# MUDE_-_Rev_A.net
KiCad netlist of a schematic drawn in EAGLE
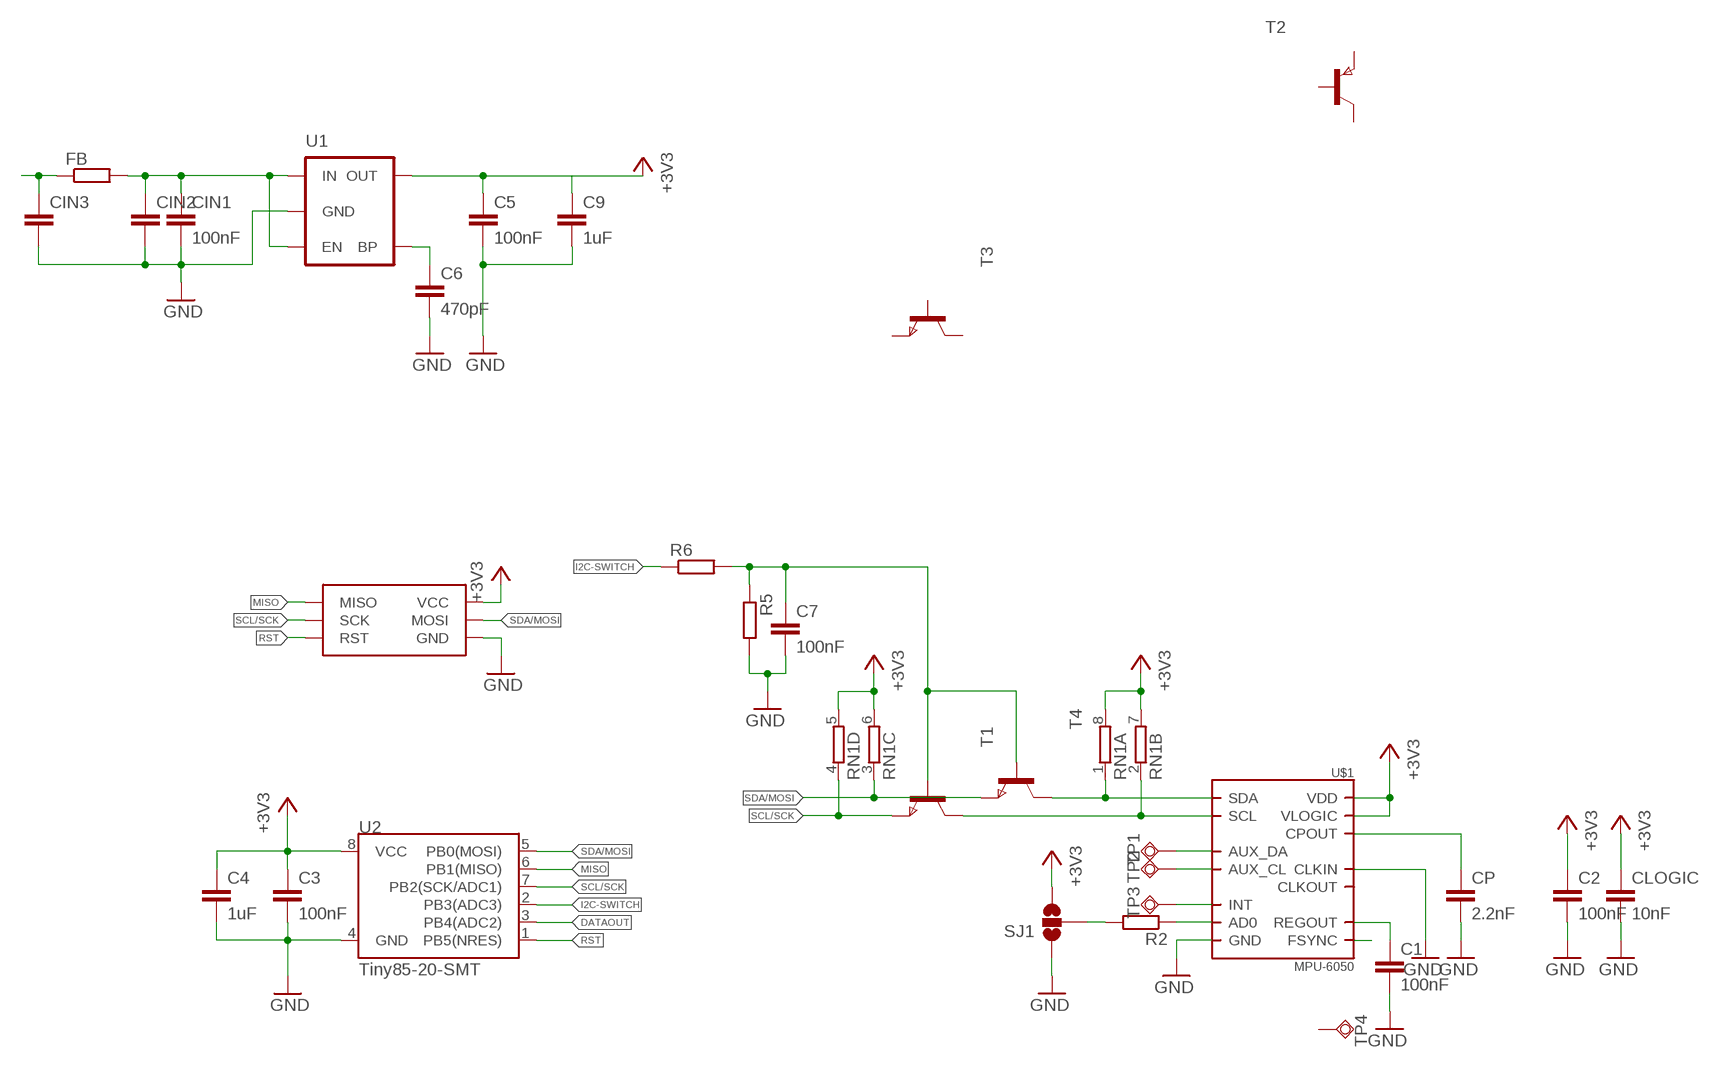
[diagram p0: schematic, sheet 1]

(export (version "E")
  (design (tool "Eeschema 10.0.6"))
  (components
    (comp (ref "C1")
      (value "100nF")
      (footprint "eagle-import:C0603")
      (libsource (lib "eagle-import") (part "C-EUC0603"))
    )
    (comp (ref "C2")
      (value "100nF")
      (footprint "eagle-import:C0603")
      (libsource (lib "eagle-import") (part "C-EUC0603"))
    )
    (comp (ref "C3")
      (value "100nF")
      (footprint "eagle-import:C0603")
      (libsource (lib "eagle-import") (part "C-EUC0603"))
    )
    (comp (ref "C4")
      (value "1uF")
      (footprint "eagle-import:C0603")
      (libsource (lib "eagle-import") (part "C-EUC0603"))
    )
    (comp (ref "C5")
      (value "100nF")
      (footprint "eagle-import:C0603")
      (libsource (lib "eagle-import") (part "C-EUC0603"))
    )
    (comp (ref "C6")
      (value "470pF")
      (footprint "eagle-import:C0603")
      (libsource (lib "eagle-import") (part "C-EUC0603"))
    )
    (comp (ref "C7")
      (value "100nF")
      (footprint "eagle-import:C0603")
      (libsource (lib "eagle-import") (part "C-EUC0603"))
    )
    (comp (ref "C9")
      (value "1uF")
      (footprint "eagle-import:C0603")
      (libsource (lib "eagle-import") (part "C-EUC0603"))
    )
    (comp (ref "CIN1")
      (value "100nF")
      (footprint "eagle-import:C0603")
      (libsource (lib "eagle-import") (part "C-EUC0603"))
    )
    (comp (ref "CIN2")
      (value "C-EUC0805")
      (footprint "eagle-import:C0805")
      (libsource (lib "eagle-import") (part "C-EUC0805"))
    )
    (comp (ref "CIN3")
      (value "C-EUC0805")
      (footprint "eagle-import:C0805")
      (libsource (lib "eagle-import") (part "C-EUC0805"))
    )
    (comp (ref "CLOGIC")
      (value "10nF")
      (footprint "eagle-import:C0603")
      (libsource (lib "eagle-import") (part "C-EUC0603"))
    )
    (comp (ref "CP")
      (value "2.2nF")
      (footprint "eagle-import:C0603")
      (libsource (lib "eagle-import") (part "C-EUC0603"))
    )
    (comp (ref "FB")
      (value "R-EU_R0603")
      (footprint "eagle-import:R0603")
      (libsource (lib "eagle-import") (part "R-EU_R0603"))
    )
    (comp (ref "R2")
      (value "R-EU_R0603")
      (footprint "eagle-import:R0603")
      (libsource (lib "eagle-import") (part "R-EU_R0603"))
    )
    (comp (ref "R5")
      (value "R-EU_R0603")
      (footprint "eagle-import:R0603")
      (libsource (lib "eagle-import") (part "R-EU_R0603"))
    )
    (comp (ref "R6")
      (value "R-EU_R0603")
      (footprint "eagle-import:R0603")
      (libsource (lib "eagle-import") (part "R-EU_R0603"))
    )
    (comp (ref "RN1")
      (value "4R-N0603-ARV")
      (footprint "eagle-import:0603-ARV")
      (libsource (lib "eagle-import") (part "4R-N0603-ARV"))
    )
    (comp (ref "SJ1")
      (value "SOLDERJUMPER_2WAYS")
      (footprint "eagle-import:SJ_3")
      (libsource (lib "eagle-import") (part "SOLDERJUMPER_2WAYS"))
    )
    (comp (ref "T1")
      (value "NPNSOT323")
      (footprint "eagle-import:SOT323")
      (fields (field (name "MPN") "DSS4160U-7"))
      (libsource (lib "eagle-import") (part "NPNSOT323"))
    )
    (comp (ref "T2")
      (value "PNPSOT323")
      (footprint "eagle-import:SOT323")
      (fields (field (name "MPN") "2DB1689-7"))
      (libsource (lib "eagle-import") (part "PNPSOT323"))
    )
    (comp (ref "T3")
      (value "NPNSOT323")
      (footprint "eagle-import:SOT323")
      (fields (field (name "MPN") "DSS4160U-7"))
      (libsource (lib "eagle-import") (part "NPNSOT323"))
    )
    (comp (ref "T4")
      (value "NPNSOT323")
      (footprint "eagle-import:SOT323")
      (fields (field (name "MPN") "DSS4160U-7"))
      (libsource (lib "eagle-import") (part "NPNSOT323"))
    )
    (comp (ref "TP1")
      (value "TPSQTP10R")
      (footprint "eagle-import:TP10R")
      (libsource (lib "eagle-import") (part "TPSQTP10R"))
    )
    (comp (ref "TP2")
      (value "TPSQTP10R")
      (footprint "eagle-import:TP10R")
      (libsource (lib "eagle-import") (part "TPSQTP10R"))
    )
    (comp (ref "TP3")
      (value "TPSQTP10R")
      (footprint "eagle-import:TP10R")
      (libsource (lib "eagle-import") (part "TPSQTP10R"))
    )
    (comp (ref "TP4")
      (value "TPSQTP14R")
      (footprint "eagle-import:TP14R")
      (libsource (lib "eagle-import") (part "TPSQTP14R"))
    )
    (comp (ref "U$1")
      (value "MPU-6050")
      (footprint "eagle-import:QFN.24.4X4")
      (libsource (lib "eagle-import") (part "MPU-6050"))
    )
    (comp (ref "U$3")
      (value "ISP_POGOISP_POGO")
      (footprint "eagle-import:ISP_POGO")
      (libsource (lib "eagle-import") (part "ISP_POGOISP_POGO"))
    )
    (comp (ref "U1")
      (value "MIC52053.3V")
      (footprint "eagle-import:SOT23-5")
      (libsource (lib "eagle-import") (part "MIC52053.3V"))
    )
    (comp (ref "U2")
      (value "Tiny85-20-SMT")
      (footprint "eagle-import:SO08-EIAJ")
      (libsource (lib "eagle-import") (part "ATTINY45TINY85-20-SMT"))
    )
  )
  (nets
    (net (code "1") (name "+3V3") (class "Default")
      (node (ref "C2") (pin "1") (pinfunction "1_1") (pintype "passive"))
      (node (ref "C3") (pin "1") (pinfunction "1_1") (pintype "passive"))
      (node (ref "C4") (pin "1") (pinfunction "1_1") (pintype "passive"))
      (node (ref "C5") (pin "1") (pinfunction "1_1") (pintype "passive"))
      (node (ref "C9") (pin "1") (pinfunction "1_1") (pintype "passive"))
      (node (ref "CLOGIC") (pin "1") (pinfunction "1_1") (pintype "passive"))
      (node (ref "RN1") (pin "5") (pinfunction "2_5") (pintype "passive"))
      (node (ref "RN1") (pin "6") (pinfunction "2_6") (pintype "passive"))
      (node (ref "RN1") (pin "7") (pinfunction "2_7") (pintype "passive"))
      (node (ref "RN1") (pin "8") (pinfunction "2_8") (pintype "passive"))
      (node (ref "SJ1") (pin "3") (pinfunction "3_3") (pintype "passive"))
      (node (ref "U$1") (pin "13") (pinfunction "VDD_13") (pintype "bidirectional"))
      (node (ref "U$1") (pin "8") (pinfunction "VLOGIC_8") (pintype "bidirectional"))
      (node (ref "U$3") (pin "VCC") (pinfunction "VCC_VCC") (pintype "bidirectional"))
      (node (ref "U1") (pin "5") (pinfunction "OUT_5") (pintype "passive"))
      (node (ref "U2") (pin "8") (pinfunction "VCC_8") (pintype "bidirectional"))
    )
    (net (code "2") (name "DATAOUT") (class "Default")
      (node (ref "U2") (pin "3") (pinfunction "PB4(ADC2)_3") (pintype "bidirectional"))
    )
    (net (code "3") (name "GND") (class "Default")
      (node (ref "C1") (pin "2") (pinfunction "2_2") (pintype "passive"))
      (node (ref "C2") (pin "2") (pinfunction "2_2") (pintype "passive"))
      (node (ref "C3") (pin "2") (pinfunction "2_2") (pintype "passive"))
      (node (ref "C4") (pin "2") (pinfunction "2_2") (pintype "passive"))
      (node (ref "C5") (pin "2") (pinfunction "2_2") (pintype "passive"))
      (node (ref "C6") (pin "2") (pinfunction "2_2") (pintype "passive"))
      (node (ref "C7") (pin "2") (pinfunction "2_2") (pintype "passive"))
      (node (ref "C9") (pin "2") (pinfunction "2_2") (pintype "passive"))
      (node (ref "CIN1") (pin "2") (pinfunction "2_2") (pintype "passive"))
      (node (ref "CIN2") (pin "2") (pinfunction "2_2") (pintype "passive"))
      (node (ref "CIN3") (pin "2") (pinfunction "2_2") (pintype "passive"))
      (node (ref "CLOGIC") (pin "2") (pinfunction "2_2") (pintype "passive"))
      (node (ref "CP") (pin "2") (pinfunction "2_2") (pintype "passive"))
      (node (ref "R5") (pin "2") (pinfunction "2_2") (pintype "passive"))
      (node (ref "SJ1") (pin "1") (pinfunction "1_1") (pintype "passive"))
      (node (ref "U$1") (pin "1") (pinfunction "CLKIN_1") (pintype "bidirectional"))
      (node (ref "U$1") (pin "18") (pinfunction "GND_18") (pintype "bidirectional"))
      (node (ref "U$3") (pin "GND") (pinfunction "GND_GND") (pintype "bidirectional"))
      (node (ref "U1") (pin "2") (pinfunction "GND_2") (pintype "input"))
      (node (ref "U2") (pin "4") (pinfunction "GND_4") (pintype "bidirectional"))
    )
    (net (code "4") (name "I2C-SWITCH") (class "Default")
      (node (ref "R6") (pin "1") (pinfunction "1_1") (pintype "passive"))
      (node (ref "U2") (pin "2") (pinfunction "PB3(ADC3)_2") (pintype "bidirectional"))
    )
    (net (code "5") (name "MISO") (class "Default")
      (node (ref "U$3") (pin "MISO") (pinfunction "MISO_MISO") (pintype "bidirectional"))
      (node (ref "U2") (pin "6") (pinfunction "PB1(MISO)_6") (pintype "bidirectional"))
    )
    (net (code "6") (name "Net-(CIN3-Pad1)") (class "Default")
      (node (ref "CIN3") (pin "1") (pinfunction "1_1") (pintype "passive"))
      (node (ref "FB") (pin "1") (pinfunction "1_1") (pintype "passive"))
    )
    (net (code "7") (name "Net-(R2-Pad2)") (class "Default")
      (node (ref "R2") (pin "2") (pinfunction "2_2") (pintype "passive"))
      (node (ref "SJ1") (pin "2") (pinfunction "2_2") (pintype "passive"))
    )
    (net (code "8") (name "Net-(RN1B-1)") (class "Default")
      (node (ref "RN1") (pin "2") (pinfunction "1_2") (pintype "passive"))
      (node (ref "T1") (pin "1") (pinfunction "C_1") (pintype "passive"))
      (node (ref "U$1") (pin "23") (pinfunction "SCL_23") (pintype "bidirectional"))
    )
    (net (code "9") (name "Net-(T1-B)") (class "Default")
      (node (ref "C7") (pin "1") (pinfunction "1_1") (pintype "passive"))
      (node (ref "R5") (pin "1") (pinfunction "1_1") (pintype "passive"))
      (node (ref "R6") (pin "2") (pinfunction "2_2") (pintype "passive"))
      (node (ref "T1") (pin "2") (pinfunction "B_2") (pintype "passive"))
      (node (ref "T4") (pin "2") (pinfunction "B_2") (pintype "passive"))
    )
    (net (code "10") (name "Net-(T4-C)") (class "Default")
      (node (ref "RN1") (pin "1") (pinfunction "1_1") (pintype "passive"))
      (node (ref "T4") (pin "1") (pinfunction "C_1") (pintype "passive"))
      (node (ref "U$1") (pin "24") (pinfunction "SDA_24") (pintype "bidirectional"))
    )
    (net (code "11") (name "Net-(U$1-AD0)") (class "Default")
      (node (ref "R2") (pin "1") (pinfunction "1_1") (pintype "passive"))
      (node (ref "U$1") (pin "9") (pinfunction "AD0_9") (pintype "bidirectional"))
    )
    (net (code "12") (name "Net-(U$1-AUX_CL)") (class "Default")
      (node (ref "TP2") (pin "TP") (pinfunction "TP_TP") (pintype "input"))
      (node (ref "U$1") (pin "7") (pinfunction "AUX_CL_7") (pintype "bidirectional"))
    )
    (net (code "13") (name "Net-(U$1-AUX_DA)") (class "Default")
      (node (ref "TP1") (pin "TP") (pinfunction "TP_TP") (pintype "input"))
      (node (ref "U$1") (pin "6") (pinfunction "AUX_DA_6") (pintype "bidirectional"))
    )
    (net (code "14") (name "Net-(U$1-CPOUT)") (class "Default")
      (node (ref "CP") (pin "1") (pinfunction "1_1") (pintype "passive"))
      (node (ref "U$1") (pin "20") (pinfunction "CPOUT_20") (pintype "bidirectional"))
    )
    (net (code "15") (name "Net-(U$1-INT)") (class "Default")
      (node (ref "TP3") (pin "TP") (pinfunction "TP_TP") (pintype "input"))
      (node (ref "U$1") (pin "12") (pinfunction "INT_12") (pintype "bidirectional"))
    )
    (net (code "16") (name "Net-(U$1-REGOUT)") (class "Default")
      (node (ref "C1") (pin "1") (pinfunction "1_1") (pintype "passive"))
      (node (ref "U$1") (pin "10") (pinfunction "REGOUT_10") (pintype "bidirectional"))
    )
    (net (code "17") (name "Net-(U1-BP)") (class "Default")
      (node (ref "C6") (pin "1") (pinfunction "1_1") (pintype "passive"))
      (node (ref "U1") (pin "4") (pinfunction "BP_4") (pintype "input"))
    )
    (net (code "18") (name "Net-(U1-EN)") (class "Default")
      (node (ref "CIN1") (pin "1") (pinfunction "1_1") (pintype "passive"))
      (node (ref "CIN2") (pin "1") (pinfunction "1_1") (pintype "passive"))
      (node (ref "FB") (pin "2") (pinfunction "2_2") (pintype "passive"))
      (node (ref "U1") (pin "1") (pinfunction "IN_1") (pintype "input"))
      (node (ref "U1") (pin "3") (pinfunction "EN_3") (pintype "input"))
    )
    (net (code "19") (name "RST") (class "Default")
      (node (ref "U$3") (pin "RST") (pinfunction "RST_RST") (pintype "bidirectional"))
      (node (ref "U2") (pin "1") (pinfunction "PB5(NRES)_1") (pintype "bidirectional"))
    )
    (net (code "20") (name "SCL{slash}SCK") (class "Default")
      (node (ref "RN1") (pin "4") (pinfunction "1_4") (pintype "passive"))
      (node (ref "T1") (pin "3") (pinfunction "E_3") (pintype "passive"))
      (node (ref "U$3") (pin "SCK") (pinfunction "SCK_SCK") (pintype "bidirectional"))
      (node (ref "U2") (pin "7") (pinfunction "PB2(SCK/ADC1)_7") (pintype "bidirectional"))
    )
    (net (code "21") (name "SDA{slash}MOSI") (class "Default")
      (node (ref "RN1") (pin "3") (pinfunction "1_3") (pintype "passive"))
      (node (ref "T4") (pin "3") (pinfunction "E_3") (pintype "passive"))
      (node (ref "U$3") (pin "MOSI") (pinfunction "MOSI_MOSI") (pintype "bidirectional"))
      (node (ref "U2") (pin "5") (pinfunction "PB0(MOSI)_5") (pintype "bidirectional"))
    )
    (net (code "22") (name "unconnected-(T2-B-Pad2)") (class "Default")
      (node (ref "T2") (pin "2") (pinfunction "B_2") (pintype "passive"))
    )
    (net (code "23") (name "unconnected-(T2-C-Pad1)") (class "Default")
      (node (ref "T2") (pin "1") (pinfunction "C_1") (pintype "passive"))
    )
    (net (code "24") (name "unconnected-(T2-E-Pad3)") (class "Default")
      (node (ref "T2") (pin "3") (pinfunction "E_3") (pintype "passive"))
    )
    (net (code "25") (name "unconnected-(T3-B-Pad2)") (class "Default")
      (node (ref "T3") (pin "2") (pinfunction "B_2") (pintype "passive"))
    )
    (net (code "26") (name "unconnected-(T3-C-Pad1)") (class "Default")
      (node (ref "T3") (pin "1") (pinfunction "C_1") (pintype "passive"))
    )
    (net (code "27") (name "unconnected-(T3-E-Pad3)") (class "Default")
      (node (ref "T3") (pin "3") (pinfunction "E_3") (pintype "passive"))
    )
    (net (code "28") (name "unconnected-(TP4-PadTP)") (class "Default")
      (node (ref "TP4") (pin "TP") (pinfunction "TP_TP") (pintype "input"))
    )
    (net (code "29") (name "unconnected-(U$1-CLKOUT-Pad22)") (class "Default")
      (node (ref "U$1") (pin "22") (pinfunction "CLKOUT_22") (pintype "bidirectional"))
    )
    (net (code "30") (name "unconnected-(U$1-FSYNC-Pad11)") (class "Default")
      (node (ref "U$1") (pin "11") (pinfunction "FSYNC_11") (pintype "bidirectional"))
    )
  )
)
